# Christmass_tree.net
KiCad netlist of a schematic drawn in EAGLE
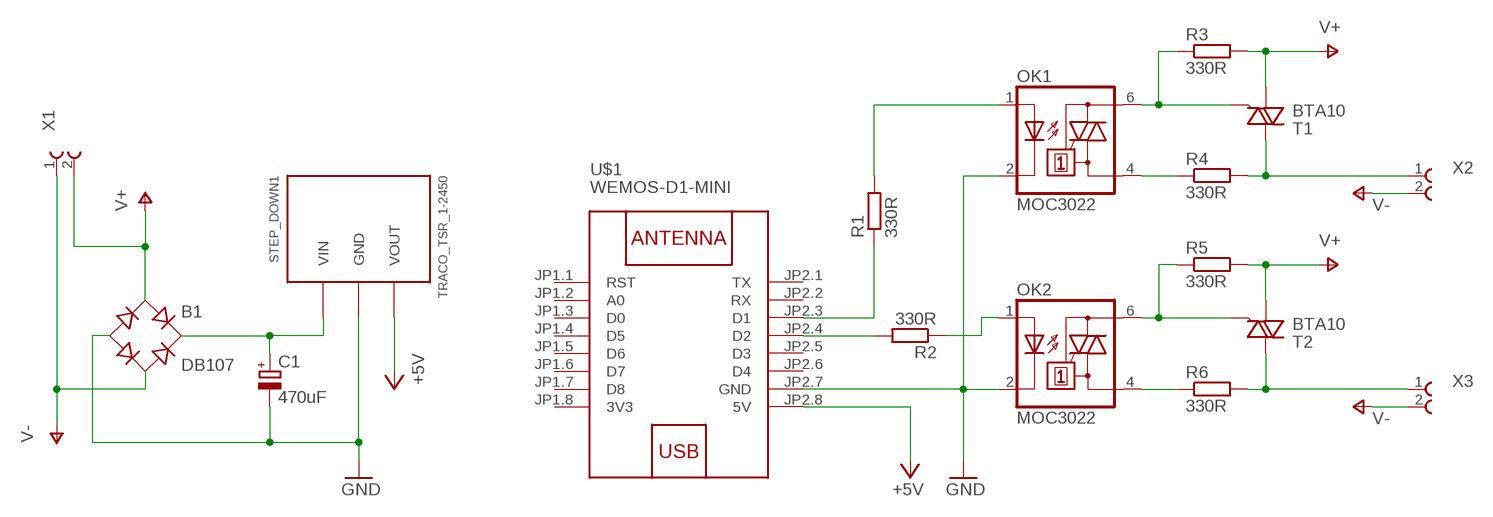
[diagram p0: schematic, sheet 1]

(export (version "E")
  (design (tool "Eeschema 10.0.6"))
  (components
    (comp (ref "B1")
      (value "DB107")
      (footprint "eagle-import:DB")
      (libsource (lib "eagle-import") (part "DB?GDB107"))
    )
    (comp (ref "C1")
      (value "470uF")
      (footprint "eagle-import:E5-10,5")
      (libsource (lib "eagle-import") (part "CPOL-EUE5-10.5"))
    )
    (comp (ref "OK1")
      (value "MOC3022")
      (footprint "eagle-import:DIL06")
      (fields (field (name "MF") "FAIRCHILD SEMICONDUCTOR") (field (name "MPN") "MOC3031M"))
      (libsource (lib "eagle-import") (part "MOC3031M"))
    )
    (comp (ref "OK2")
      (value "MOC3022")
      (footprint "eagle-import:DIL06")
      (fields (field (name "MF") "FAIRCHILD SEMICONDUCTOR") (field (name "MPN") "MOC3031M"))
      (libsource (lib "eagle-import") (part "MOC3031M"))
    )
    (comp (ref "R1")
      (value "330R")
      (footprint "eagle-import:0204_7")
      (libsource (lib "eagle-import") (part "R-EU_0204/7"))
    )
    (comp (ref "R2")
      (value "330R")
      (footprint "eagle-import:0204_7")
      (libsource (lib "eagle-import") (part "R-EU_0204/7"))
    )
    (comp (ref "R3")
      (value "330R")
      (footprint "eagle-import:0204_7")
      (libsource (lib "eagle-import") (part "R-EU_0204/7"))
    )
    (comp (ref "R4")
      (value "330R")
      (footprint "eagle-import:0204_7")
      (libsource (lib "eagle-import") (part "R-EU_0204/7"))
    )
    (comp (ref "R5")
      (value "330R")
      (footprint "eagle-import:0204_7")
      (libsource (lib "eagle-import") (part "R-EU_0204/7"))
    )
    (comp (ref "R6")
      (value "330R")
      (footprint "eagle-import:0204_7")
      (libsource (lib "eagle-import") (part "R-EU_0204/7"))
    )
    (comp (ref "STEP_DOWN1")
      (value "TRACO_TSR_1-2450")
      (footprint "eagle-import:TRACO_TSR_1-2450")
      (libsource (lib "eagle-import") (part "TRACO_TSR_1-2450"))
    )
    (comp (ref "T1")
      (value "BTA10")
      (footprint "eagle-import:TO218DS")
      (libsource (lib "eagle-import") (part "TIC253"))
    )
    (comp (ref "T2")
      (value "BTA10")
      (footprint "eagle-import:TO218DS")
      (libsource (lib "eagle-import") (part "TIC253"))
    )
    (comp (ref "U$1")
      (value "WEMOS-D1-MINI")
      (footprint "eagle-import:WEMOS-D1-MINI_BEZ")
      (libsource (lib "eagle-import") (part "WEMOS-D1-MINIBEZ_POTISKU"))
    )
    (comp (ref "X1")
      (value "2PIN_5MM_TERMINAL")
      (footprint "eagle-import:2PIN_5MM_TERMMINAL")
      (libsource (lib "eagle-import") (part "2PIN_5MM_TERMINAL"))
    )
    (comp (ref "X2")
      (value "2PIN_5MM_TERMINAL")
      (footprint "eagle-import:2PIN_5MM_TERMMINAL")
      (libsource (lib "eagle-import") (part "2PIN_5MM_TERMINAL"))
    )
    (comp (ref "X3")
      (value "2PIN_5MM_TERMINAL")
      (footprint "eagle-import:2PIN_5MM_TERMMINAL")
      (libsource (lib "eagle-import") (part "2PIN_5MM_TERMINAL"))
    )
  )
  (nets
    (net (code "1") (name "+5V") (class "Default")
      (node (ref "STEP_DOWN1") (pin "VOUT") (pinfunction "VOUT_VOUT") (pintype "output"))
      (node (ref "U$1") (pin "JP2.8") (pinfunction "5V_JP2.8") (pintype "power_in"))
    )
    (net (code "2") (name "/3V3") (class "Default")
      (node (ref "U$1") (pin "JP1.8") (pinfunction "3V3_JP1.8") (pintype "power_in"))
    )
    (net (code "3") (name "GND") (class "Default")
      (node (ref "B1") (pin "-") (pinfunction "-_-") (pintype "passive"))
      (node (ref "C1") (pin "-") (pinfunction "-_-") (pintype "passive"))
      (node (ref "OK1") (pin "2") (pinfunction "C_2") (pintype "passive"))
      (node (ref "OK2") (pin "2") (pinfunction "C_2") (pintype "passive"))
      (node (ref "STEP_DOWN1") (pin "GND") (pinfunction "GND_GND") (pintype "bidirectional"))
      (node (ref "U$1") (pin "JP2.7") (pinfunction "GND_JP2.7") (pintype "power_in"))
    )
    (net (code "4") (name "Net-(B1-Pad+)") (class "Default")
      (node (ref "B1") (pin "+") (pinfunction "+_+") (pintype "passive"))
      (node (ref "C1") (pin "+") (pinfunction "+_+") (pintype "passive"))
      (node (ref "STEP_DOWN1") (pin "VIN") (pinfunction "VIN_VIN") (pintype "input"))
    )
    (net (code "5") (name "Net-(OK1-A)") (class "Default")
      (node (ref "OK1") (pin "1") (pinfunction "A_1") (pintype "passive"))
      (node (ref "R1") (pin "2") (pinfunction "2_2") (pintype "passive"))
    )
    (net (code "6") (name "Net-(OK1-A1)") (class "Default")
      (node (ref "OK1") (pin "4") (pinfunction "A1_4") (pintype "passive"))
      (node (ref "R4") (pin "1") (pinfunction "1_1") (pintype "passive"))
    )
    (net (code "7") (name "Net-(OK1-A2)") (class "Default")
      (node (ref "OK1") (pin "6") (pinfunction "A2_6") (pintype "passive"))
      (node (ref "R3") (pin "1") (pinfunction "1_1") (pintype "passive"))
      (node (ref "T1") (pin "G") (pinfunction "G_G") (pintype "passive"))
    )
    (net (code "8") (name "Net-(OK2-A)") (class "Default")
      (node (ref "OK2") (pin "1") (pinfunction "A_1") (pintype "passive"))
      (node (ref "R2") (pin "1") (pinfunction "1_1") (pintype "passive"))
    )
    (net (code "9") (name "Net-(OK2-A1)") (class "Default")
      (node (ref "OK2") (pin "4") (pinfunction "A1_4") (pintype "passive"))
      (node (ref "R6") (pin "1") (pinfunction "1_1") (pintype "passive"))
    )
    (net (code "10") (name "Net-(OK2-A2)") (class "Default")
      (node (ref "OK2") (pin "6") (pinfunction "A2_6") (pintype "passive"))
      (node (ref "R5") (pin "1") (pinfunction "1_1") (pintype "passive"))
      (node (ref "T2") (pin "G") (pinfunction "G_G") (pintype "passive"))
    )
    (net (code "11") (name "Net-(R4-Pad2)") (class "Default")
      (node (ref "R4") (pin "2") (pinfunction "2_2") (pintype "passive"))
      (node (ref "T1") (pin "A2") (pinfunction "A2_A2") (pintype "passive"))
      (node (ref "X2") (pin "1") (pinfunction "1_1") (pintype "passive"))
    )
    (net (code "12") (name "Net-(R6-Pad2)") (class "Default")
      (node (ref "R6") (pin "2") (pinfunction "2_2") (pintype "passive"))
      (node (ref "T2") (pin "A2") (pinfunction "A2_A2") (pintype "passive"))
      (node (ref "X3") (pin "1") (pinfunction "1_1") (pintype "passive"))
    )
    (net (code "13") (name "Net-(U$1-D1)") (class "Default")
      (node (ref "R1") (pin "1") (pinfunction "1_1") (pintype "passive"))
      (node (ref "U$1") (pin "JP2.3") (pinfunction "D1_JP2.3") (pintype "bidirectional"))
    )
    (net (code "14") (name "Net-(U$1-D2)") (class "Default")
      (node (ref "R2") (pin "2") (pinfunction "2_2") (pintype "passive"))
      (node (ref "U$1") (pin "JP2.4") (pinfunction "D2_JP2.4") (pintype "bidirectional"))
    )
    (net (code "15") (name "V+") (class "Default")
      (node (ref "B1") (pin "AC1") (pinfunction "AC1_AC1") (pintype "passive"))
      (node (ref "R3") (pin "2") (pinfunction "2_2") (pintype "passive"))
      (node (ref "R5") (pin "2") (pinfunction "2_2") (pintype "passive"))
      (node (ref "T1") (pin "A1") (pinfunction "A1_A1") (pintype "passive"))
      (node (ref "T2") (pin "A1") (pinfunction "A1_A1") (pintype "passive"))
      (node (ref "X1") (pin "2") (pinfunction "2_2") (pintype "passive"))
    )
    (net (code "16") (name "V-") (class "Default")
      (node (ref "B1") (pin "AC2") (pinfunction "AC2_AC2") (pintype "passive"))
      (node (ref "X1") (pin "1") (pinfunction "1_1") (pintype "passive"))
      (node (ref "X2") (pin "2") (pinfunction "2_2") (pintype "passive"))
      (node (ref "X3") (pin "2") (pinfunction "2_2") (pintype "passive"))
    )
    (net (code "17") (name "unconnected-(U$1-A0-PadJP1.2)") (class "Default")
      (node (ref "U$1") (pin "JP1.2") (pinfunction "A0_JP1.2") (pintype "bidirectional"))
    )
    (net (code "18") (name "unconnected-(U$1-D0-PadJP1.3)") (class "Default")
      (node (ref "U$1") (pin "JP1.3") (pinfunction "D0_JP1.3") (pintype "bidirectional"))
    )
    (net (code "19") (name "unconnected-(U$1-D3-PadJP2.5)") (class "Default")
      (node (ref "U$1") (pin "JP2.5") (pinfunction "D3_JP2.5") (pintype "bidirectional"))
    )
    (net (code "20") (name "unconnected-(U$1-D4-PadJP2.6)") (class "Default")
      (node (ref "U$1") (pin "JP2.6") (pinfunction "D4_JP2.6") (pintype "bidirectional"))
    )
    (net (code "21") (name "unconnected-(U$1-D5-PadJP1.4)") (class "Default")
      (node (ref "U$1") (pin "JP1.4") (pinfunction "D5_JP1.4") (pintype "bidirectional"))
    )
    (net (code "22") (name "unconnected-(U$1-D6-PadJP1.5)") (class "Default")
      (node (ref "U$1") (pin "JP1.5") (pinfunction "D6_JP1.5") (pintype "bidirectional"))
    )
    (net (code "23") (name "unconnected-(U$1-D7-PadJP1.6)") (class "Default")
      (node (ref "U$1") (pin "JP1.6") (pinfunction "D7_JP1.6") (pintype "bidirectional"))
    )
    (net (code "24") (name "unconnected-(U$1-D8-PadJP1.7)") (class "Default")
      (node (ref "U$1") (pin "JP1.7") (pinfunction "D8_JP1.7") (pintype "bidirectional"))
    )
    (net (code "25") (name "unconnected-(U$1-RST-PadJP1.1)") (class "Default")
      (node (ref "U$1") (pin "JP1.1") (pinfunction "RST_JP1.1") (pintype "bidirectional"))
    )
    (net (code "26") (name "unconnected-(U$1-RX-PadJP2.2)") (class "Default")
      (node (ref "U$1") (pin "JP2.2") (pinfunction "RX_JP2.2") (pintype "bidirectional"))
    )
    (net (code "27") (name "unconnected-(U$1-TX-PadJP2.1)") (class "Default")
      (node (ref "U$1") (pin "JP2.1") (pinfunction "TX_JP2.1") (pintype "bidirectional"))
    )
  )
)
